# SCH_Mathushigan_s-PCB_2024-10-10.net
KiCad netlist of a schematic drawn in EasyEDA
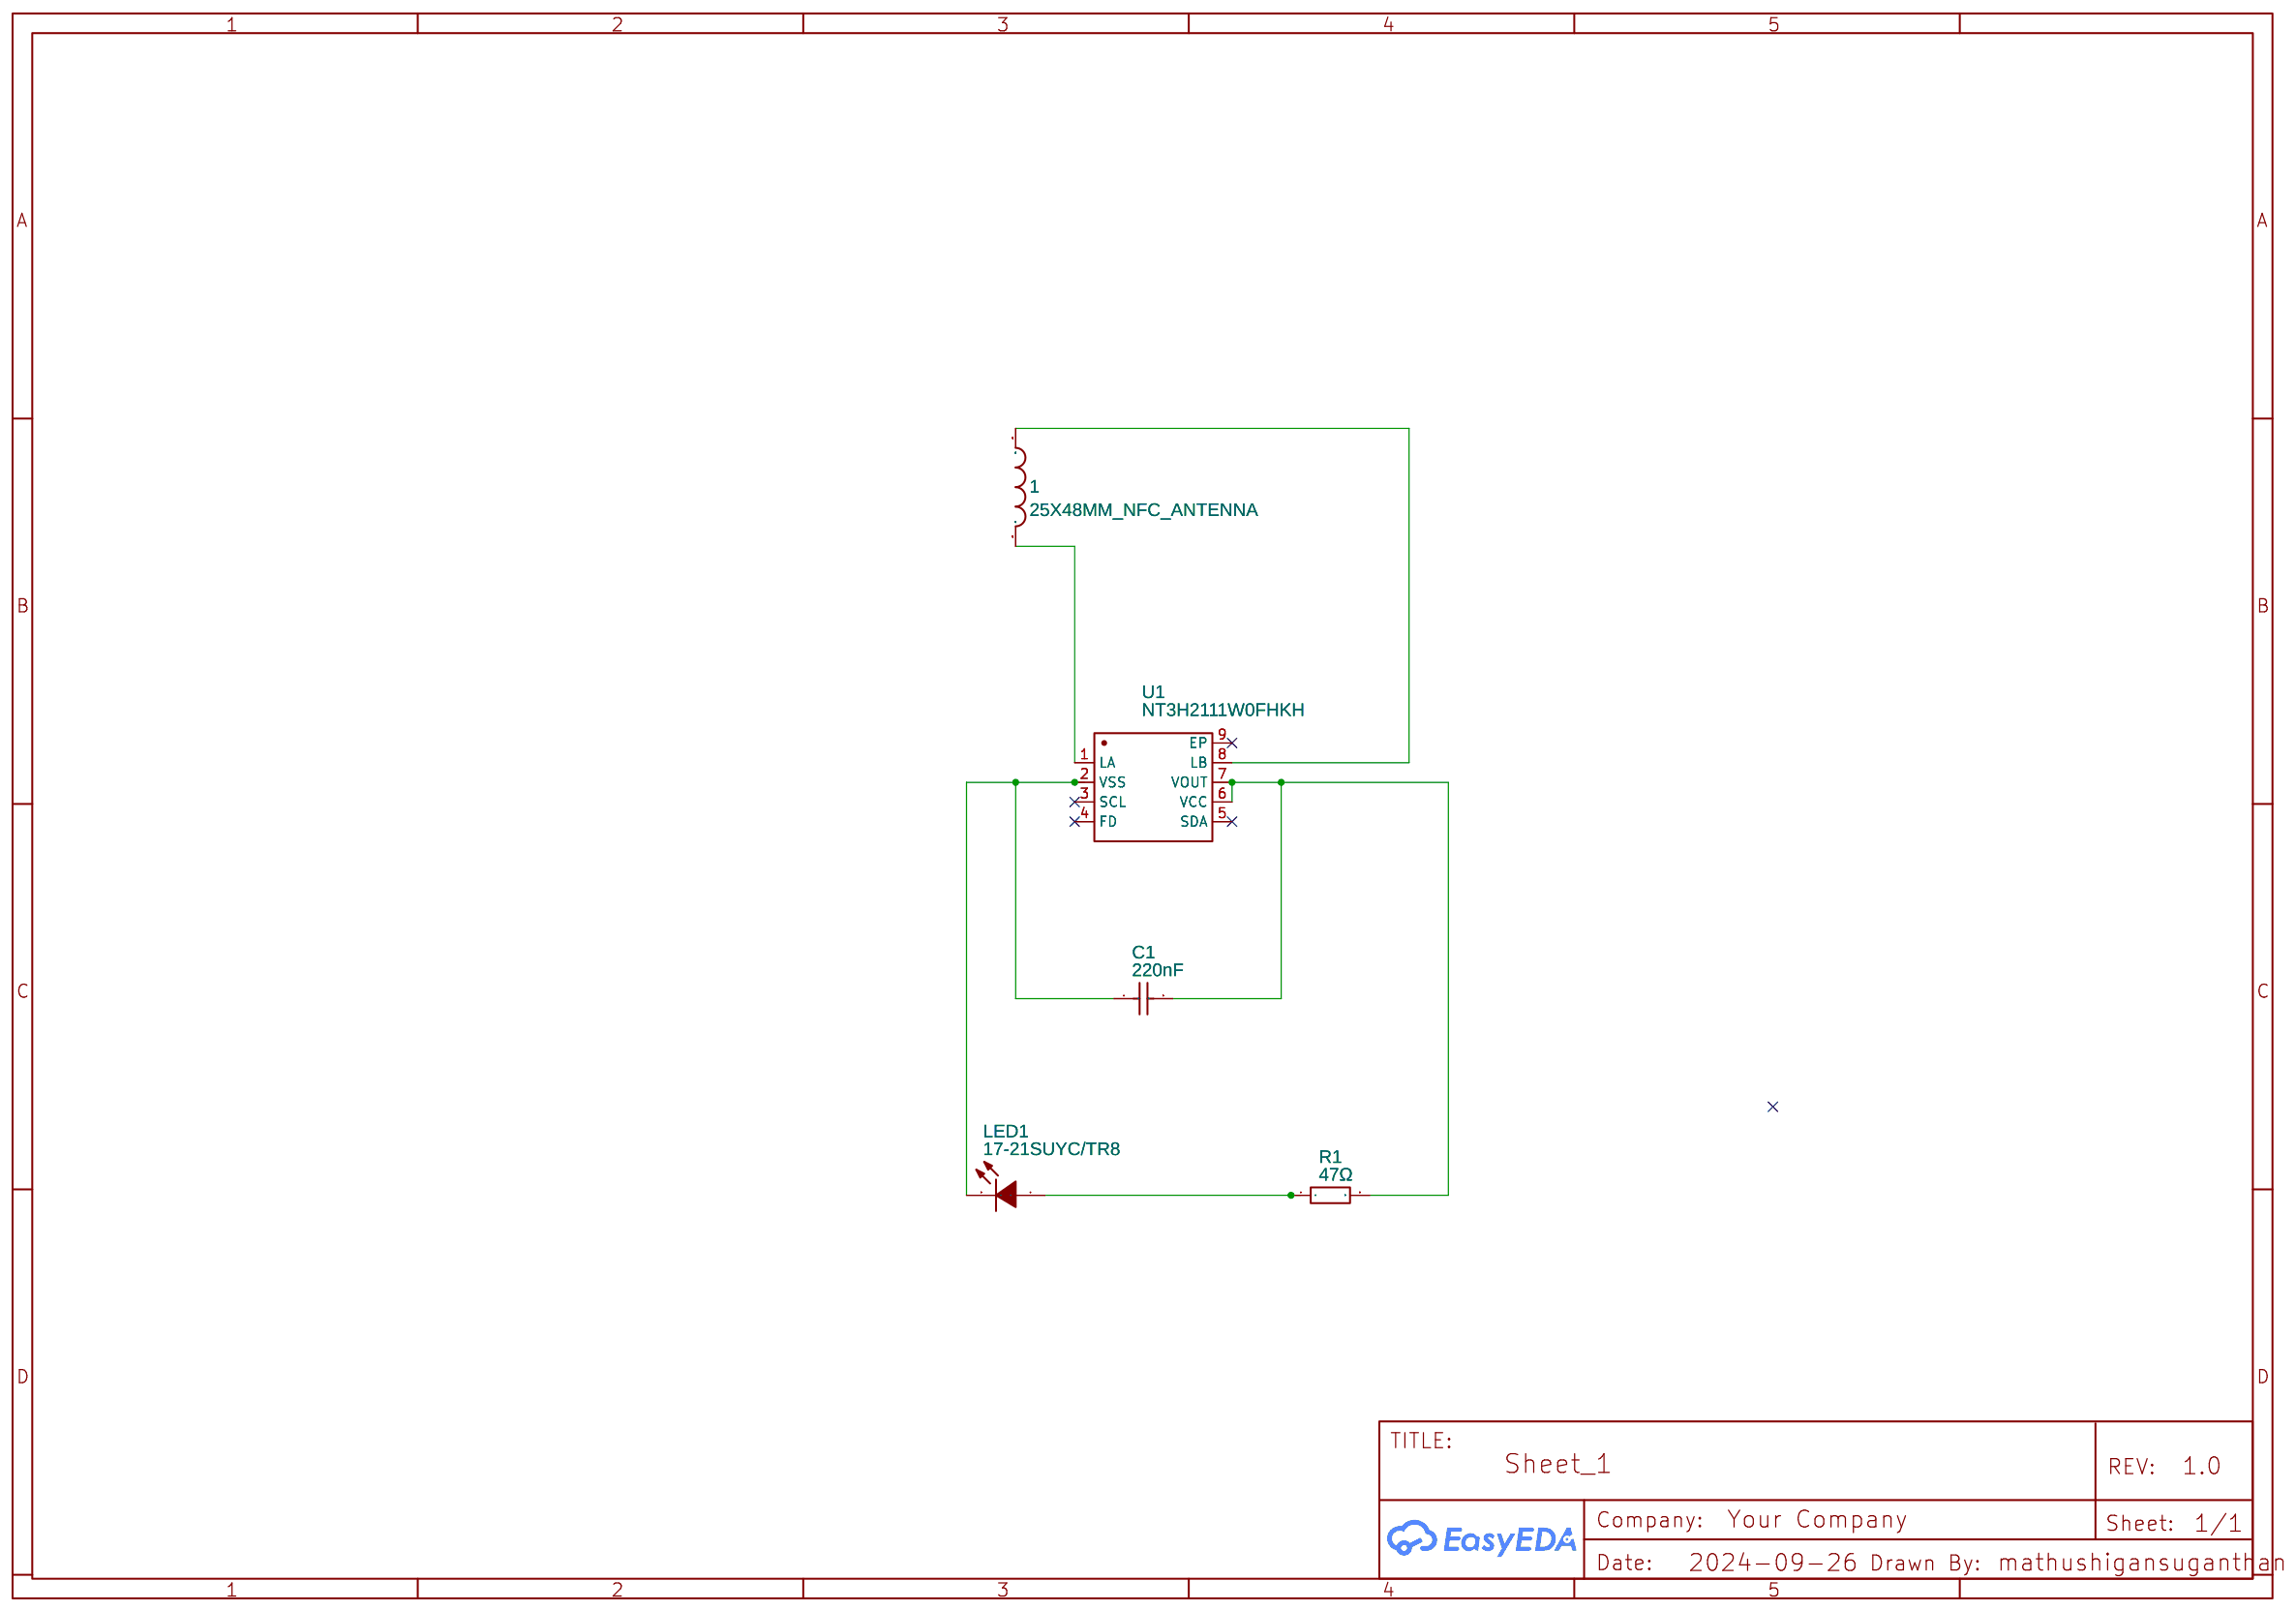
[diagram p0: schematic sheet]

(export (version "E")
  (design (tool "Eeschema 10.0.6"))
  (components
    (comp (ref "1") (value "25X48MM_NFC_ANTENNA") (libsource (lib "") (part "25X48MM_NFC_ANTENNA")))
    (comp (ref "C1")
      (value "220nF")
      (fields
        (field (name "Manufacturer Part") "CL10B224KA8NNNC")
        (field (name "Manufacturer") "SAMSUNG(三星)")
      )
      (libsource (lib "") (part "CL10B224KA8NNNC"))
    )
    (comp (ref "LED1")
      (value "17-21SUYC/TR8")
      (fields (field (name "Manufacturer Part") "KT-0805黄灯") (field (name "Manufacturer") "KENTO"))
      (libsource (lib "") (part "17-21SUYC/TR8"))
    )
    (comp (ref "R1")
      (value "47Ω")
      (fields
        (field (name "Manufacturer Part") "0603WAF470JT5E")
        (field (name "Manufacturer") "UNI-ROYAL(厚声)")
      )
      (libsource (lib "") (part "0603WAF470JT5E"))
    )
    (comp (ref "U1")
      (value "NT3H2111W0FHKH")
      (fields (field (name "Manufacturer") "NXP(恩智浦)"))
      (libsource (lib "") (part "NT3H2111W0FHKH"))
    )
  )
  (nets
    (net (code "1") (name "Net-(LED1-+)") (class "Default")
      (node (ref "LED1") (pin "1") (pinfunction "+_1") (pintype "unspecified"))
      (node (ref "R1") (pin "1") (pinfunction "1_1") (pintype "input"))
    )
    (net (code "2") (name "Net-(LED1--)") (class "Default")
      (node (ref "C1") (pin "1") (pinfunction "1_1") (pintype "input"))
      (node (ref "LED1") (pin "2") (pinfunction "-_2") (pintype "unspecified"))
      (node (ref "U1") (pin "2") (pinfunction "VSS_2") (pintype "unspecified"))
    )
    (net (code "3") (name "Net-(U1-LA)") (class "Default")
      (node (ref "1") (pin "P$2") (pinfunction "P$2_P$2") (pintype "bidirectional"))
      (node (ref "U1") (pin "1") (pinfunction "LA_1") (pintype "unspecified"))
    )
    (net (code "4") (name "Net-(U1-LB)") (class "Default")
      (node (ref "1") (pin "P$1") (pinfunction "P$1_P$1") (pintype "bidirectional"))
      (node (ref "U1") (pin "8") (pinfunction "LB_8") (pintype "unspecified"))
    )
    (net (code "5") (name "Net-(U1-VCC)") (class "Default")
      (node (ref "C1") (pin "2") (pinfunction "2_2") (pintype "input"))
      (node (ref "R1") (pin "2") (pinfunction "2_2") (pintype "input"))
      (node (ref "U1") (pin "6") (pinfunction "VCC_6") (pintype "unspecified"))
      (node (ref "U1") (pin "7") (pinfunction "VOUT_7") (pintype "unspecified"))
    )
    (net (code "6") (name "unconnected-(U1-EP-Pad9)") (class "Default")
      (node (ref "U1") (pin "9") (pinfunction "EP_9") (pintype "unspecified+no_connect"))
    )
    (net (code "7") (name "unconnected-(U1-FD-Pad4)") (class "Default")
      (node (ref "U1") (pin "4") (pinfunction "FD_4") (pintype "unspecified+no_connect"))
    )
    (net (code "8") (name "unconnected-(U1-SCL-Pad3)") (class "Default")
      (node (ref "U1") (pin "3") (pinfunction "SCL_3") (pintype "unspecified+no_connect"))
    )
    (net (code "9") (name "unconnected-(U1-SDA-Pad5)") (class "Default")
      (node (ref "U1") (pin "5") (pinfunction "SDA_5") (pintype "unspecified+no_connect"))
    )
  )
)
